# Muller-C1.net
KiCad netlist of a schematic drawn in Altium Designer
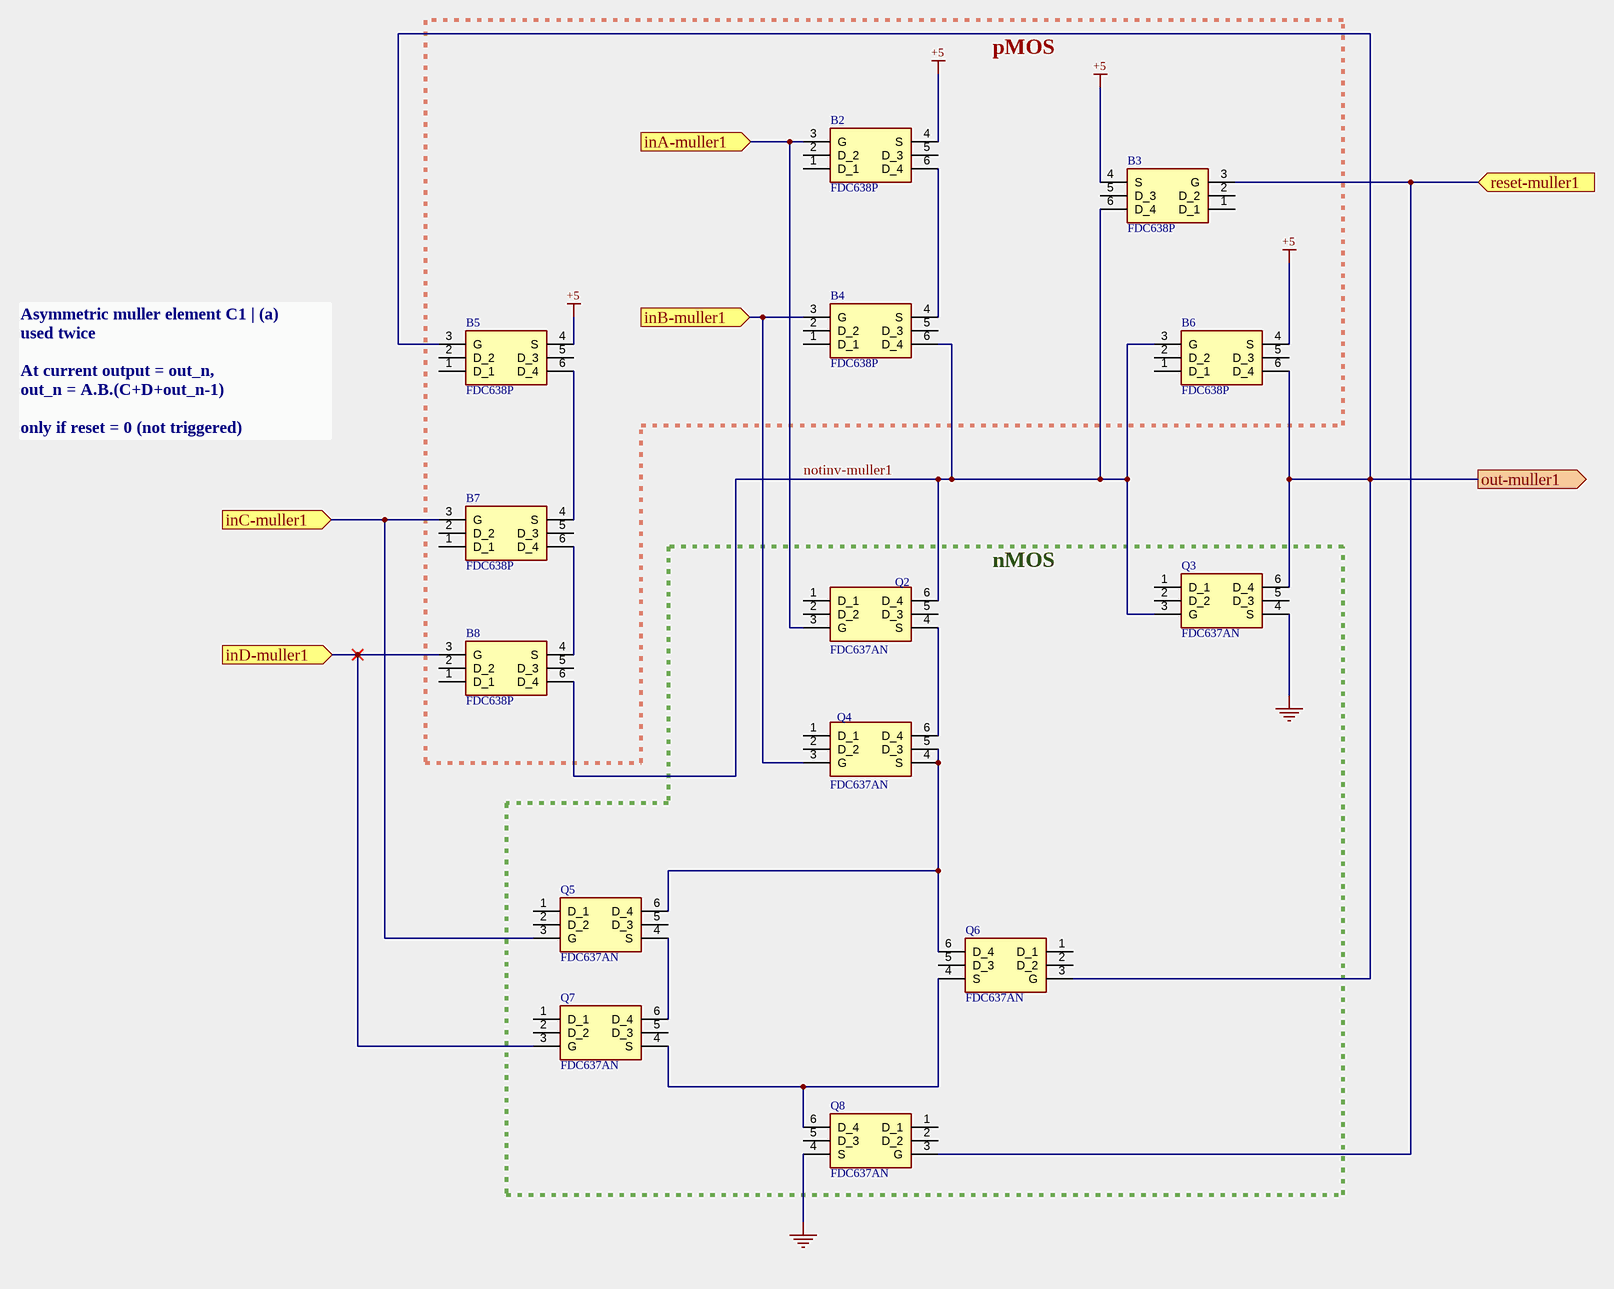
[diagram p0: Muller-C1.SchDoc]

(export (version "E")
  (design (tool "Eeschema 10.0.6"))
  (components
    (comp (ref "B2")
      (value "FDC638P")
      (footprint "SOT95P275X110-6N")
      (description "Low gate charge (10 nC typical)")
      (fields (field (name "MOUSER PART NUMBER") "512-FDC638P"))
      (libsource (lib "iloke") (part "FDC638P"))
    )
    (comp (ref "B3")
      (value "FDC638P")
      (footprint "SOT95P275X110-6N")
      (description "Low gate charge (10 nC typical)")
      (fields (field (name "MOUSER PART NUMBER") "512-FDC638P"))
      (libsource (lib "") (part "FDC638P_1"))
    )
    (comp (ref "B4")
      (value "FDC638P")
      (footprint "SOT95P275X110-6N")
      (description "Low gate charge (10 nC typical)")
      (fields (field (name "MOUSER PART NUMBER") "512-FDC638P"))
      (libsource (lib "iloke") (part "FDC638P"))
    )
    (comp (ref "B5")
      (value "FDC638P")
      (footprint "SOT95P275X110-6N")
      (description "Low gate charge (10 nC typical)")
      (fields (field (name "MOUSER PART NUMBER") "512-FDC638P"))
      (libsource (lib "iloke") (part "FDC638P"))
    )
    (comp (ref "B6")
      (value "FDC638P")
      (footprint "SOT95P275X110-6N")
      (description "Low gate charge (10 nC typical)")
      (fields (field (name "MOUSER PART NUMBER") "512-FDC638P"))
      (libsource (lib "iloke") (part "FDC638P"))
    )
    (comp (ref "B7")
      (value "FDC638P")
      (footprint "SOT95P275X110-6N")
      (description "Low gate charge (10 nC typical)")
      (fields (field (name "MOUSER PART NUMBER") "512-FDC638P"))
      (libsource (lib "iloke") (part "FDC638P"))
    )
    (comp (ref "B8")
      (value "FDC638P")
      (footprint "SOT95P275X110-6N")
      (description "Low gate charge (10 nC typical)")
      (fields (field (name "MOUSER PART NUMBER") "512-FDC638P"))
      (libsource (lib "iloke") (part "FDC638P"))
    )
    (comp (ref "Q2")
      (value "FDC637AN")
      (footprint "SOT95P275X110-6N")
      (description "Low gate charge (10.5nC typical).")
      (fields (field (name "MOUSER PART NUMBER") "512-FDC637AN"))
      (libsource (lib "iloke") (part "FDC637AN"))
    )
    (comp (ref "Q3")
      (value "FDC637AN")
      (footprint "SOT95P275X110-6N")
      (description "Low gate charge (10.5nC typical).")
      (fields (field (name "MOUSER PART NUMBER") "512-FDC637AN"))
      (libsource (lib "iloke") (part "FDC637AN"))
    )
    (comp (ref "Q4")
      (value "FDC637AN")
      (footprint "SOT95P275X110-6N")
      (description "Low gate charge (10.5nC typical).")
      (fields (field (name "MOUSER PART NUMBER") "512-FDC637AN"))
      (libsource (lib "iloke") (part "FDC637AN"))
    )
    (comp (ref "Q5")
      (value "FDC637AN")
      (footprint "SOT95P275X110-6N")
      (description "Low gate charge (10.5nC typical).")
      (fields (field (name "MOUSER PART NUMBER") "512-FDC637AN"))
      (libsource (lib "iloke") (part "FDC637AN"))
    )
    (comp (ref "Q6")
      (value "FDC637AN")
      (footprint "SOT95P275X110-6N")
      (description "Low gate charge (10.5nC typical).")
      (fields (field (name "MOUSER PART NUMBER") "512-FDC637AN"))
      (libsource (lib "") (part "FDC637AN_1"))
    )
    (comp (ref "Q7")
      (value "FDC637AN")
      (footprint "SOT95P275X110-6N")
      (description "Low gate charge (10.5nC typical).")
      (fields (field (name "MOUSER PART NUMBER") "512-FDC637AN"))
      (libsource (lib "iloke") (part "FDC637AN"))
    )
    (comp (ref "Q8")
      (value "FDC637AN")
      (footprint "SOT95P275X110-6N")
      (description "Low gate charge (10.5nC typical).")
      (fields (field (name "MOUSER PART NUMBER") "512-FDC637AN"))
      (libsource (lib "") (part "FDC637AN_1"))
    )
  )
  (nets
    (net (code "1") (name "+5") (class "Default")
      (node (ref "B2") (pin "4") (pinfunction "S_4") (pintype "passive"))
      (node (ref "B3") (pin "4") (pinfunction "S_4") (pintype "passive"))
      (node (ref "B5") (pin "4") (pinfunction "S_4") (pintype "passive"))
      (node (ref "B6") (pin "4") (pinfunction "S_4") (pintype "passive"))
    )
    (net (code "2") (name "/inA-muller1") (class "Default")
      (node (ref "B2") (pin "3") (pinfunction "G_3") (pintype "passive"))
      (node (ref "Q2") (pin "3") (pinfunction "G_3") (pintype "passive"))
    )
    (net (code "3") (name "/inB-muller1") (class "Default")
      (node (ref "B4") (pin "3") (pinfunction "G_3") (pintype "passive"))
      (node (ref "Q4") (pin "3") (pinfunction "G_3") (pintype "passive"))
    )
    (net (code "4") (name "/inC-muller1") (class "Default")
      (node (ref "B7") (pin "3") (pinfunction "G_3") (pintype "passive"))
      (node (ref "Q5") (pin "3") (pinfunction "G_3") (pintype "passive"))
    )
    (net (code "5") (name "/inD-muller1") (class "Default")
      (node (ref "B8") (pin "3") (pinfunction "G_3") (pintype "passive"))
      (node (ref "Q7") (pin "3") (pinfunction "G_3") (pintype "passive"))
    )
    (net (code "6") (name "/notinv-muller1") (class "Default")
      (node (ref "B3") (pin "6") (pinfunction "D_4_6") (pintype "passive"))
      (node (ref "B4") (pin "6") (pinfunction "D_4_6") (pintype "passive"))
      (node (ref "B6") (pin "3") (pinfunction "G_3") (pintype "passive"))
      (node (ref "B8") (pin "6") (pinfunction "D_4_6") (pintype "passive"))
      (node (ref "Q2") (pin "6") (pinfunction "D_4_6") (pintype "passive"))
      (node (ref "Q3") (pin "3") (pinfunction "G_3") (pintype "passive"))
    )
    (net (code "7") (name "/out-muller1") (class "Default")
      (node (ref "B5") (pin "3") (pinfunction "G_3") (pintype "passive"))
      (node (ref "B6") (pin "6") (pinfunction "D_4_6") (pintype "passive"))
      (node (ref "Q3") (pin "6") (pinfunction "D_4_6") (pintype "passive"))
      (node (ref "Q6") (pin "3") (pinfunction "G_3") (pintype "passive"))
    )
    (net (code "8") (name "/reset-muller1") (class "Default")
      (node (ref "B3") (pin "3") (pinfunction "G_3") (pintype "passive"))
      (node (ref "Q8") (pin "3") (pinfunction "G_3") (pintype "passive"))
    )
    (net (code "9") (name "GND") (class "Default")
      (node (ref "Q3") (pin "4") (pinfunction "S_4") (pintype "passive"))
      (node (ref "Q8") (pin "4") (pinfunction "S_4") (pintype "passive"))
    )
    (net (code "10") (name "Net-(B2-D_4)") (class "Default")
      (node (ref "B2") (pin "6") (pinfunction "D_4_6") (pintype "passive"))
      (node (ref "B4") (pin "4") (pinfunction "S_4") (pintype "passive"))
    )
    (net (code "11") (name "Net-(B5-D_4)") (class "Default")
      (node (ref "B5") (pin "6") (pinfunction "D_4_6") (pintype "passive"))
      (node (ref "B7") (pin "4") (pinfunction "S_4") (pintype "passive"))
    )
    (net (code "12") (name "Net-(B7-D_4)") (class "Default")
      (node (ref "B7") (pin "6") (pinfunction "D_4_6") (pintype "passive"))
      (node (ref "B8") (pin "4") (pinfunction "S_4") (pintype "passive"))
    )
    (net (code "13") (name "Net-(Q2-S)") (class "Default")
      (node (ref "Q2") (pin "4") (pinfunction "S_4") (pintype "passive"))
      (node (ref "Q4") (pin "6") (pinfunction "D_4_6") (pintype "passive"))
    )
    (net (code "14") (name "Net-(Q4-D_3)") (class "Default")
      (node (ref "Q4") (pin "4") (pinfunction "S_4") (pintype "passive"))
      (node (ref "Q4") (pin "5") (pinfunction "D_3_5") (pintype "passive"))
      (node (ref "Q5") (pin "6") (pinfunction "D_4_6") (pintype "passive"))
      (node (ref "Q6") (pin "6") (pinfunction "D_4_6") (pintype "passive"))
    )
    (net (code "15") (name "Net-(Q5-S)") (class "Default")
      (node (ref "Q5") (pin "4") (pinfunction "S_4") (pintype "passive"))
      (node (ref "Q7") (pin "6") (pinfunction "D_4_6") (pintype "passive"))
    )
    (net (code "16") (name "Net-(Q6-S)") (class "Default")
      (node (ref "Q6") (pin "4") (pinfunction "S_4") (pintype "passive"))
      (node (ref "Q7") (pin "4") (pinfunction "S_4") (pintype "passive"))
      (node (ref "Q8") (pin "6") (pinfunction "D_4_6") (pintype "passive"))
    )
    (net (code "17") (name "unconnected-(B2-D_1-Pad1)") (class "Default")
      (node (ref "B2") (pin "1") (pinfunction "D_1_1") (pintype "passive"))
    )
    (net (code "18") (name "unconnected-(B2-D_2-Pad2)") (class "Default")
      (node (ref "B2") (pin "2") (pinfunction "D_2_2") (pintype "passive"))
    )
    (net (code "19") (name "unconnected-(B2-D_3-Pad5)") (class "Default")
      (node (ref "B2") (pin "5") (pinfunction "D_3_5") (pintype "passive"))
    )
    (net (code "20") (name "unconnected-(B3-D_1-Pad1)") (class "Default")
      (node (ref "B3") (pin "1") (pinfunction "D_1_1") (pintype "passive"))
    )
    (net (code "21") (name "unconnected-(B3-D_2-Pad2)") (class "Default")
      (node (ref "B3") (pin "2") (pinfunction "D_2_2") (pintype "passive"))
    )
    (net (code "22") (name "unconnected-(B3-D_3-Pad5)") (class "Default")
      (node (ref "B3") (pin "5") (pinfunction "D_3_5") (pintype "passive"))
    )
    (net (code "23") (name "unconnected-(B4-D_1-Pad1)") (class "Default")
      (node (ref "B4") (pin "1") (pinfunction "D_1_1") (pintype "passive"))
    )
    (net (code "24") (name "unconnected-(B4-D_2-Pad2)") (class "Default")
      (node (ref "B4") (pin "2") (pinfunction "D_2_2") (pintype "passive"))
    )
    (net (code "25") (name "unconnected-(B4-D_3-Pad5)") (class "Default")
      (node (ref "B4") (pin "5") (pinfunction "D_3_5") (pintype "passive"))
    )
    (net (code "26") (name "unconnected-(B5-D_1-Pad1)") (class "Default")
      (node (ref "B5") (pin "1") (pinfunction "D_1_1") (pintype "passive"))
    )
    (net (code "27") (name "unconnected-(B5-D_2-Pad2)") (class "Default")
      (node (ref "B5") (pin "2") (pinfunction "D_2_2") (pintype "passive"))
    )
    (net (code "28") (name "unconnected-(B5-D_3-Pad5)") (class "Default")
      (node (ref "B5") (pin "5") (pinfunction "D_3_5") (pintype "passive"))
    )
    (net (code "29") (name "unconnected-(B6-D_1-Pad1)") (class "Default")
      (node (ref "B6") (pin "1") (pinfunction "D_1_1") (pintype "passive"))
    )
    (net (code "30") (name "unconnected-(B6-D_2-Pad2)") (class "Default")
      (node (ref "B6") (pin "2") (pinfunction "D_2_2") (pintype "passive"))
    )
    (net (code "31") (name "unconnected-(B6-D_3-Pad5)") (class "Default")
      (node (ref "B6") (pin "5") (pinfunction "D_3_5") (pintype "passive"))
    )
    (net (code "32") (name "unconnected-(B7-D_1-Pad1)") (class "Default")
      (node (ref "B7") (pin "1") (pinfunction "D_1_1") (pintype "passive"))
    )
    (net (code "33") (name "unconnected-(B7-D_2-Pad2)") (class "Default")
      (node (ref "B7") (pin "2") (pinfunction "D_2_2") (pintype "passive"))
    )
    (net (code "34") (name "unconnected-(B7-D_3-Pad5)") (class "Default")
      (node (ref "B7") (pin "5") (pinfunction "D_3_5") (pintype "passive"))
    )
    (net (code "35") (name "unconnected-(B8-D_1-Pad1)") (class "Default")
      (node (ref "B8") (pin "1") (pinfunction "D_1_1") (pintype "passive"))
    )
    (net (code "36") (name "unconnected-(B8-D_2-Pad2)") (class "Default")
      (node (ref "B8") (pin "2") (pinfunction "D_2_2") (pintype "passive"))
    )
    (net (code "37") (name "unconnected-(B8-D_3-Pad5)") (class "Default")
      (node (ref "B8") (pin "5") (pinfunction "D_3_5") (pintype "passive"))
    )
    (net (code "38") (name "unconnected-(Q2-D_1-Pad1)") (class "Default")
      (node (ref "Q2") (pin "1") (pinfunction "D_1_1") (pintype "passive"))
    )
    (net (code "39") (name "unconnected-(Q2-D_2-Pad2)") (class "Default")
      (node (ref "Q2") (pin "2") (pinfunction "D_2_2") (pintype "passive"))
    )
    (net (code "40") (name "unconnected-(Q2-D_3-Pad5)") (class "Default")
      (node (ref "Q2") (pin "5") (pinfunction "D_3_5") (pintype "passive"))
    )
    (net (code "41") (name "unconnected-(Q3-D_1-Pad1)") (class "Default")
      (node (ref "Q3") (pin "1") (pinfunction "D_1_1") (pintype "passive"))
    )
    (net (code "42") (name "unconnected-(Q3-D_2-Pad2)") (class "Default")
      (node (ref "Q3") (pin "2") (pinfunction "D_2_2") (pintype "passive"))
    )
    (net (code "43") (name "unconnected-(Q3-D_3-Pad5)") (class "Default")
      (node (ref "Q3") (pin "5") (pinfunction "D_3_5") (pintype "passive"))
    )
    (net (code "44") (name "unconnected-(Q4-D_1-Pad1)") (class "Default")
      (node (ref "Q4") (pin "1") (pinfunction "D_1_1") (pintype "passive"))
    )
    (net (code "45") (name "unconnected-(Q4-D_2-Pad2)") (class "Default")
      (node (ref "Q4") (pin "2") (pinfunction "D_2_2") (pintype "passive"))
    )
    (net (code "46") (name "unconnected-(Q5-D_1-Pad1)") (class "Default")
      (node (ref "Q5") (pin "1") (pinfunction "D_1_1") (pintype "passive"))
    )
    (net (code "47") (name "unconnected-(Q5-D_2-Pad2)") (class "Default")
      (node (ref "Q5") (pin "2") (pinfunction "D_2_2") (pintype "passive"))
    )
    (net (code "48") (name "unconnected-(Q5-D_3-Pad5)") (class "Default")
      (node (ref "Q5") (pin "5") (pinfunction "D_3_5") (pintype "passive"))
    )
    (net (code "49") (name "unconnected-(Q6-D_1-Pad1)") (class "Default")
      (node (ref "Q6") (pin "1") (pinfunction "D_1_1") (pintype "passive"))
    )
    (net (code "50") (name "unconnected-(Q6-D_2-Pad2)") (class "Default")
      (node (ref "Q6") (pin "2") (pinfunction "D_2_2") (pintype "passive"))
    )
    (net (code "51") (name "unconnected-(Q6-D_3-Pad5)") (class "Default")
      (node (ref "Q6") (pin "5") (pinfunction "D_3_5") (pintype "passive"))
    )
    (net (code "52") (name "unconnected-(Q7-D_1-Pad1)") (class "Default")
      (node (ref "Q7") (pin "1") (pinfunction "D_1_1") (pintype "passive"))
    )
    (net (code "53") (name "unconnected-(Q7-D_2-Pad2)") (class "Default")
      (node (ref "Q7") (pin "2") (pinfunction "D_2_2") (pintype "passive"))
    )
    (net (code "54") (name "unconnected-(Q7-D_3-Pad5)") (class "Default")
      (node (ref "Q7") (pin "5") (pinfunction "D_3_5") (pintype "passive"))
    )
    (net (code "55") (name "unconnected-(Q8-D_1-Pad1)") (class "Default")
      (node (ref "Q8") (pin "1") (pinfunction "D_1_1") (pintype "passive"))
    )
    (net (code "56") (name "unconnected-(Q8-D_2-Pad2)") (class "Default")
      (node (ref "Q8") (pin "2") (pinfunction "D_2_2") (pintype "passive"))
    )
    (net (code "57") (name "unconnected-(Q8-D_3-Pad5)") (class "Default")
      (node (ref "Q8") (pin "5") (pinfunction "D_3_5") (pintype "passive"))
    )
  )
)
